# p128.net
KiCad netlist of a schematic drawn in EAGLE
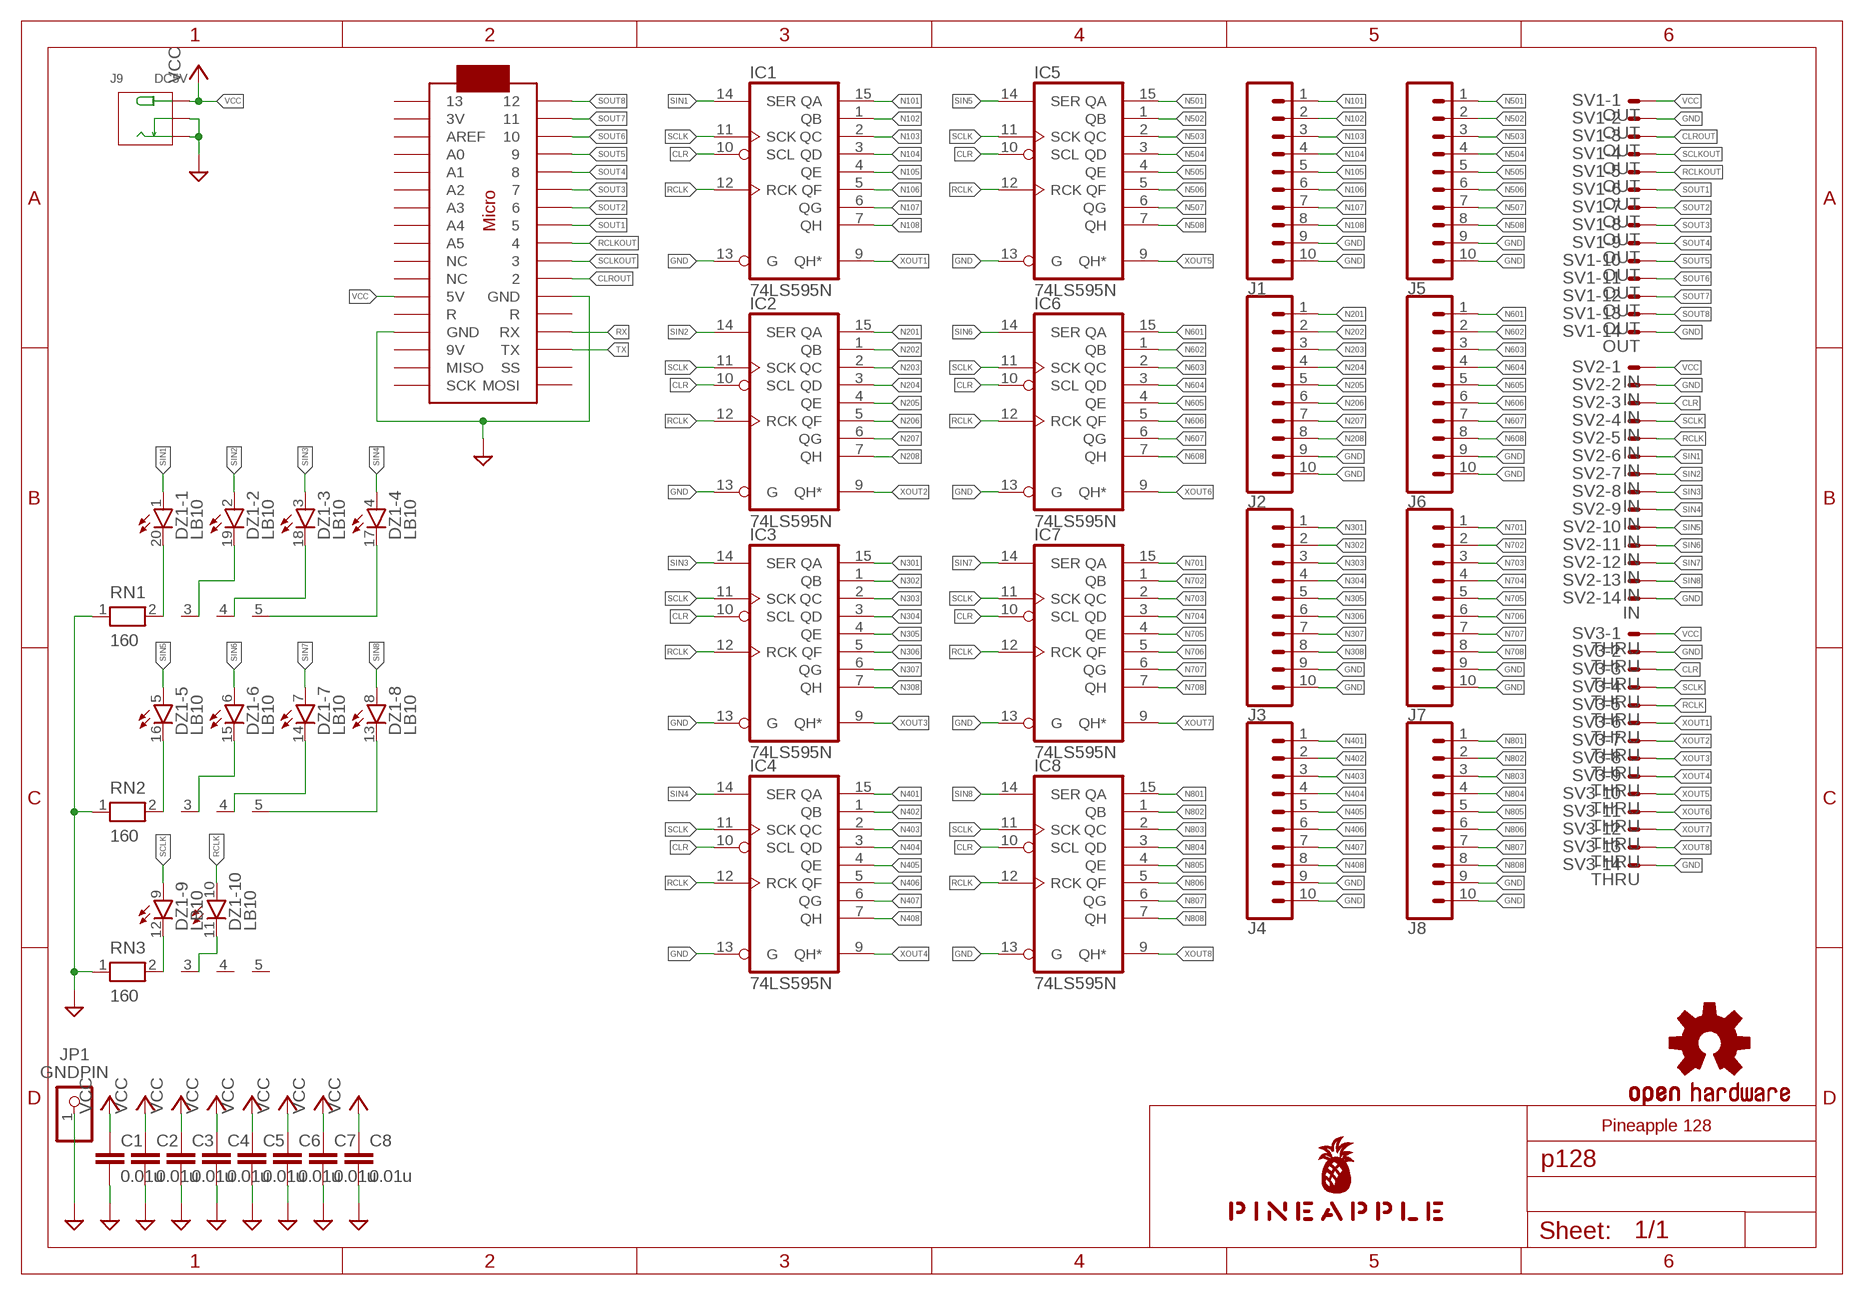
[diagram p0: schematic, sheet 1]

(export (version "E")
  (design (tool "Eeschema 10.0.6"))
  (components
    (comp (ref "C1")
      (value "0.01u")
      (footprint "eagle-import:C025-024X044")
      (libsource (lib "eagle-import") (part "C-EU025-024X044"))
    )
    (comp (ref "C2")
      (value "0.01u")
      (footprint "eagle-import:C025-024X044")
      (libsource (lib "eagle-import") (part "C-EU025-024X044"))
    )
    (comp (ref "C3")
      (value "0.01u")
      (footprint "eagle-import:C025-024X044")
      (libsource (lib "eagle-import") (part "C-EU025-024X044"))
    )
    (comp (ref "C4")
      (value "0.01u")
      (footprint "eagle-import:C025-024X044")
      (libsource (lib "eagle-import") (part "C-EU025-024X044"))
    )
    (comp (ref "C5")
      (value "0.01u")
      (footprint "eagle-import:C025-024X044")
      (libsource (lib "eagle-import") (part "C-EU025-024X044"))
    )
    (comp (ref "C6")
      (value "0.01u")
      (footprint "eagle-import:C025-024X044")
      (libsource (lib "eagle-import") (part "C-EU025-024X044"))
    )
    (comp (ref "C7")
      (value "0.01u")
      (footprint "eagle-import:C025-024X044")
      (libsource (lib "eagle-import") (part "C-EU025-024X044"))
    )
    (comp (ref "C8")
      (value "0.01u")
      (footprint "eagle-import:C025-024X044")
      (libsource (lib "eagle-import") (part "C-EU025-024X044"))
    )
    (comp (ref "DZ1")
      (value "LB10")
      (footprint "eagle-import:LB10")
      (libsource (lib "eagle-import") (part "LB10"))
    )
    (comp (ref "IC1")
      (value "74LS595N")
      (footprint "eagle-import:DIL16")
      (libsource (lib "eagle-import") (part "74595NLS"))
    )
    (comp (ref "IC2")
      (value "74LS595N")
      (footprint "eagle-import:DIL16")
      (libsource (lib "eagle-import") (part "74595NLS"))
    )
    (comp (ref "IC3")
      (value "74LS595N")
      (footprint "eagle-import:DIL16")
      (libsource (lib "eagle-import") (part "74595NLS"))
    )
    (comp (ref "IC4")
      (value "74LS595N")
      (footprint "eagle-import:DIL16")
      (libsource (lib "eagle-import") (part "74595NLS"))
    )
    (comp (ref "IC5")
      (value "74LS595N")
      (footprint "eagle-import:DIL16")
      (libsource (lib "eagle-import") (part "74595NLS"))
    )
    (comp (ref "IC6")
      (value "74LS595N")
      (footprint "eagle-import:DIL16")
      (libsource (lib "eagle-import") (part "74595NLS"))
    )
    (comp (ref "IC7")
      (value "74LS595N")
      (footprint "eagle-import:DIL16")
      (libsource (lib "eagle-import") (part "74595NLS"))
    )
    (comp (ref "IC8")
      (value "74LS595N")
      (footprint "eagle-import:DIL16")
      (libsource (lib "eagle-import") (part "74595NLS"))
    )
    (comp (ref "J1")
      (value "CONN_10\"")
      (footprint "eagle-import:1X10")
      (libsource (lib "eagle-import") (part "CONN_10{dblquote}"))
    )
    (comp (ref "J2")
      (value "CONN_10\"")
      (footprint "eagle-import:1X10")
      (libsource (lib "eagle-import") (part "CONN_10{dblquote}"))
    )
    (comp (ref "J3")
      (value "CONN_10\"")
      (footprint "eagle-import:1X10")
      (libsource (lib "eagle-import") (part "CONN_10{dblquote}"))
    )
    (comp (ref "J4")
      (value "CONN_10\"")
      (footprint "eagle-import:1X10")
      (libsource (lib "eagle-import") (part "CONN_10{dblquote}"))
    )
    (comp (ref "J5")
      (value "CONN_10\"")
      (footprint "eagle-import:1X10")
      (libsource (lib "eagle-import") (part "CONN_10{dblquote}"))
    )
    (comp (ref "J6")
      (value "CONN_10\"")
      (footprint "eagle-import:1X10")
      (libsource (lib "eagle-import") (part "CONN_10{dblquote}"))
    )
    (comp (ref "J7")
      (value "CONN_10\"")
      (footprint "eagle-import:1X10")
      (libsource (lib "eagle-import") (part "CONN_10{dblquote}"))
    )
    (comp (ref "J8")
      (value "CONN_10\"")
      (footprint "eagle-import:1X10")
      (libsource (lib "eagle-import") (part "CONN_10{dblquote}"))
    )
    (comp (ref "J9")
      (value "DC5V")
      (footprint "eagle-import:3P-L14.2_W11.0_H9.0MM")
      (libsource (lib "eagle-import") (part "JACK-DC-005'DC-005'"))
    )
    (comp (ref "JP1")
      (value "GNDPIN")
      (footprint "eagle-import:1X01")
      (libsource (lib "eagle-import") (part "PINHD-1X1"))
    )
    (comp (ref "LOGO1")
      (value "OSHW-LOGOS-COPPER")
      (footprint "eagle-import:OSHW-LOGO-S_COPPER")
      (libsource (lib "eagle-import") (part "OSHW-LOGOS-COPPER"))
    )
    (comp (ref "RN1")
      (value "160")
      (footprint "eagle-import:RN-5")
      (libsource (lib "eagle-import") (part "RN04"))
    )
    (comp (ref "RN2")
      (value "160")
      (footprint "eagle-import:RN-5")
      (libsource (lib "eagle-import") (part "RN04"))
    )
    (comp (ref "RN3")
      (value "160")
      (footprint "eagle-import:RN-5")
      (libsource (lib "eagle-import") (part "RN04"))
    )
    (comp (ref "SV1")
      (value "OUT")
      (footprint "eagle-import:ML14")
      (libsource (lib "eagle-import") (part "ML14E"))
    )
    (comp (ref "SV2")
      (value "IN")
      (footprint "eagle-import:ML14")
      (libsource (lib "eagle-import") (part "ML14E"))
    )
    (comp (ref "SV3")
      (value "THRU")
      (footprint "eagle-import:ML14")
      (libsource (lib "eagle-import") (part "ML14E"))
    )
    (comp (ref "U$1")
      (value "PINEAPPLE450_SILK")
      (footprint "eagle-import:PINEAPPLE450_SILK")
      (libsource (lib "eagle-import") (part "PINEAPPLE450_SILK"))
    )
    (comp (ref "U$2")
      (value "ARDUINOMICRO")
      (footprint "eagle-import:ARDUINOMICRO")
      (libsource (lib "eagle-import") (part "ARDUINOMICRO"))
    )
  )
  (nets
    (net (code "1") (name "CLR") (class "Default")
      (node (ref "IC1") (pin "10") (pinfunction "SCL_10") (pintype "input"))
      (node (ref "IC2") (pin "10") (pinfunction "SCL_10") (pintype "input"))
      (node (ref "IC3") (pin "10") (pinfunction "SCL_10") (pintype "input"))
      (node (ref "IC4") (pin "10") (pinfunction "SCL_10") (pintype "input"))
      (node (ref "IC5") (pin "10") (pinfunction "SCL_10") (pintype "input"))
      (node (ref "IC6") (pin "10") (pinfunction "SCL_10") (pintype "input"))
      (node (ref "IC7") (pin "10") (pinfunction "SCL_10") (pintype "input"))
      (node (ref "IC8") (pin "10") (pinfunction "SCL_10") (pintype "input"))
      (node (ref "SV2") (pin "3") (pinfunction "S_3") (pintype "passive"))
      (node (ref "SV3") (pin "3") (pinfunction "S_3") (pintype "passive"))
    )
    (net (code "2") (name "CLROUT") (class "Default")
      (node (ref "SV1") (pin "3") (pinfunction "S_3") (pintype "passive"))
      (node (ref "U$2") (pin "P$11") (pinfunction "2_P$11") (pintype "bidirectional"))
    )
    (net (code "3") (name "GND") (class "Default")
      (node (ref "C1") (pin "2") (pinfunction "2_2") (pintype "passive"))
      (node (ref "C2") (pin "2") (pinfunction "2_2") (pintype "passive"))
      (node (ref "C3") (pin "2") (pinfunction "2_2") (pintype "passive"))
      (node (ref "C4") (pin "2") (pinfunction "2_2") (pintype "passive"))
      (node (ref "C5") (pin "2") (pinfunction "2_2") (pintype "passive"))
      (node (ref "C6") (pin "2") (pinfunction "2_2") (pintype "passive"))
      (node (ref "C7") (pin "2") (pinfunction "2_2") (pintype "passive"))
      (node (ref "C8") (pin "2") (pinfunction "2_2") (pintype "passive"))
      (node (ref "IC1") (pin "13") (pinfunction "G_13") (pintype "input"))
      (node (ref "IC2") (pin "13") (pinfunction "G_13") (pintype "input"))
      (node (ref "IC3") (pin "13") (pinfunction "G_13") (pintype "input"))
      (node (ref "IC4") (pin "13") (pinfunction "G_13") (pintype "input"))
      (node (ref "IC5") (pin "13") (pinfunction "G_13") (pintype "input"))
      (node (ref "IC6") (pin "13") (pinfunction "G_13") (pintype "input"))
      (node (ref "IC7") (pin "13") (pinfunction "G_13") (pintype "input"))
      (node (ref "IC8") (pin "13") (pinfunction "G_13") (pintype "input"))
      (node (ref "J1") (pin "10") (pinfunction "10_10") (pintype "passive"))
      (node (ref "J1") (pin "9") (pinfunction "9_9") (pintype "passive"))
      (node (ref "J2") (pin "10") (pinfunction "10_10") (pintype "passive"))
      (node (ref "J2") (pin "9") (pinfunction "9_9") (pintype "passive"))
      (node (ref "J3") (pin "10") (pinfunction "10_10") (pintype "passive"))
      (node (ref "J3") (pin "9") (pinfunction "9_9") (pintype "passive"))
      (node (ref "J4") (pin "10") (pinfunction "10_10") (pintype "passive"))
      (node (ref "J4") (pin "9") (pinfunction "9_9") (pintype "passive"))
      (node (ref "J5") (pin "10") (pinfunction "10_10") (pintype "passive"))
      (node (ref "J5") (pin "9") (pinfunction "9_9") (pintype "passive"))
      (node (ref "J6") (pin "10") (pinfunction "10_10") (pintype "passive"))
      (node (ref "J6") (pin "9") (pinfunction "9_9") (pintype "passive"))
      (node (ref "J7") (pin "10") (pinfunction "10_10") (pintype "passive"))
      (node (ref "J7") (pin "9") (pinfunction "9_9") (pintype "passive"))
      (node (ref "J8") (pin "10") (pinfunction "10_10") (pintype "passive"))
      (node (ref "J8") (pin "9") (pinfunction "9_9") (pintype "passive"))
      (node (ref "J9") (pin "-1") (pinfunction "-_-1") (pintype "bidirectional"))
      (node (ref "J9") (pin "-2") (pinfunction "CDN_-2") (pintype "bidirectional"))
      (node (ref "JP1") (pin "1") (pinfunction "1_1") (pintype "passive"))
      (node (ref "RN1") (pin "1") (pinfunction "1_1") (pintype "passive"))
      (node (ref "RN2") (pin "1") (pinfunction "1_1") (pintype "passive"))
      (node (ref "RN3") (pin "1") (pinfunction "1_1") (pintype "passive"))
      (node (ref "SV1") (pin "14") (pinfunction "S_14") (pintype "passive"))
      (node (ref "SV1") (pin "2") (pinfunction "S_2") (pintype "passive"))
      (node (ref "SV2") (pin "14") (pinfunction "S_14") (pintype "passive"))
      (node (ref "SV2") (pin "2") (pinfunction "S_2") (pintype "passive"))
      (node (ref "SV3") (pin "14") (pinfunction "S_14") (pintype "passive"))
      (node (ref "SV3") (pin "2") (pinfunction "S_2") (pintype "passive"))
      (node (ref "U$2") (pin "P$12") (pinfunction "GND_P$12") (pintype "bidirectional"))
      (node (ref "U$2") (pin "P$21") (pinfunction "GND_P$21") (pintype "bidirectional"))
    )
    (net (code "4") (name "N101") (class "Default")
      (node (ref "IC1") (pin "15") (pinfunction "QA_15") (pintype "tri_state"))
      (node (ref "J1") (pin "1") (pinfunction "1_1") (pintype "passive"))
    )
    (net (code "5") (name "N102") (class "Default")
      (node (ref "IC1") (pin "1") (pinfunction "QB_1") (pintype "tri_state"))
      (node (ref "J1") (pin "2") (pinfunction "2_2") (pintype "passive"))
    )
    (net (code "6") (name "N103") (class "Default")
      (node (ref "IC1") (pin "2") (pinfunction "QC_2") (pintype "tri_state"))
      (node (ref "J1") (pin "3") (pinfunction "3_3") (pintype "passive"))
    )
    (net (code "7") (name "N104") (class "Default")
      (node (ref "IC1") (pin "3") (pinfunction "QD_3") (pintype "tri_state"))
      (node (ref "J1") (pin "4") (pinfunction "4_4") (pintype "passive"))
    )
    (net (code "8") (name "N105") (class "Default")
      (node (ref "IC1") (pin "4") (pinfunction "QE_4") (pintype "tri_state"))
      (node (ref "J1") (pin "5") (pinfunction "5_5") (pintype "passive"))
    )
    (net (code "9") (name "N106") (class "Default")
      (node (ref "IC1") (pin "5") (pinfunction "QF_5") (pintype "tri_state"))
      (node (ref "J1") (pin "6") (pinfunction "6_6") (pintype "passive"))
    )
    (net (code "10") (name "N107") (class "Default")
      (node (ref "IC1") (pin "6") (pinfunction "QG_6") (pintype "tri_state"))
      (node (ref "J1") (pin "7") (pinfunction "7_7") (pintype "passive"))
    )
    (net (code "11") (name "N108") (class "Default")
      (node (ref "IC1") (pin "7") (pinfunction "QH_7") (pintype "tri_state"))
      (node (ref "J1") (pin "8") (pinfunction "8_8") (pintype "passive"))
    )
    (net (code "12") (name "N201") (class "Default")
      (node (ref "IC2") (pin "15") (pinfunction "QA_15") (pintype "tri_state"))
      (node (ref "J2") (pin "1") (pinfunction "1_1") (pintype "passive"))
    )
    (net (code "13") (name "N202") (class "Default")
      (node (ref "IC2") (pin "1") (pinfunction "QB_1") (pintype "tri_state"))
      (node (ref "J2") (pin "2") (pinfunction "2_2") (pintype "passive"))
    )
    (net (code "14") (name "N203") (class "Default")
      (node (ref "IC2") (pin "2") (pinfunction "QC_2") (pintype "tri_state"))
      (node (ref "J2") (pin "3") (pinfunction "3_3") (pintype "passive"))
    )
    (net (code "15") (name "N204") (class "Default")
      (node (ref "IC2") (pin "3") (pinfunction "QD_3") (pintype "tri_state"))
      (node (ref "J2") (pin "4") (pinfunction "4_4") (pintype "passive"))
    )
    (net (code "16") (name "N205") (class "Default")
      (node (ref "IC2") (pin "4") (pinfunction "QE_4") (pintype "tri_state"))
      (node (ref "J2") (pin "5") (pinfunction "5_5") (pintype "passive"))
    )
    (net (code "17") (name "N206") (class "Default")
      (node (ref "IC2") (pin "5") (pinfunction "QF_5") (pintype "tri_state"))
      (node (ref "J2") (pin "6") (pinfunction "6_6") (pintype "passive"))
    )
    (net (code "18") (name "N207") (class "Default")
      (node (ref "IC2") (pin "6") (pinfunction "QG_6") (pintype "tri_state"))
      (node (ref "J2") (pin "7") (pinfunction "7_7") (pintype "passive"))
    )
    (net (code "19") (name "N208") (class "Default")
      (node (ref "IC2") (pin "7") (pinfunction "QH_7") (pintype "tri_state"))
      (node (ref "J2") (pin "8") (pinfunction "8_8") (pintype "passive"))
    )
    (net (code "20") (name "N301") (class "Default")
      (node (ref "IC3") (pin "15") (pinfunction "QA_15") (pintype "tri_state"))
      (node (ref "J3") (pin "1") (pinfunction "1_1") (pintype "passive"))
    )
    (net (code "21") (name "N302") (class "Default")
      (node (ref "IC3") (pin "1") (pinfunction "QB_1") (pintype "tri_state"))
      (node (ref "J3") (pin "2") (pinfunction "2_2") (pintype "passive"))
    )
    (net (code "22") (name "N303") (class "Default")
      (node (ref "IC3") (pin "2") (pinfunction "QC_2") (pintype "tri_state"))
      (node (ref "J3") (pin "3") (pinfunction "3_3") (pintype "passive"))
    )
    (net (code "23") (name "N304") (class "Default")
      (node (ref "IC3") (pin "3") (pinfunction "QD_3") (pintype "tri_state"))
      (node (ref "J3") (pin "4") (pinfunction "4_4") (pintype "passive"))
    )
    (net (code "24") (name "N305") (class "Default")
      (node (ref "IC3") (pin "4") (pinfunction "QE_4") (pintype "tri_state"))
      (node (ref "J3") (pin "5") (pinfunction "5_5") (pintype "passive"))
    )
    (net (code "25") (name "N306") (class "Default")
      (node (ref "IC3") (pin "5") (pinfunction "QF_5") (pintype "tri_state"))
      (node (ref "J3") (pin "6") (pinfunction "6_6") (pintype "passive"))
    )
    (net (code "26") (name "N307") (class "Default")
      (node (ref "IC3") (pin "6") (pinfunction "QG_6") (pintype "tri_state"))
      (node (ref "J3") (pin "7") (pinfunction "7_7") (pintype "passive"))
    )
    (net (code "27") (name "N308") (class "Default")
      (node (ref "IC3") (pin "7") (pinfunction "QH_7") (pintype "tri_state"))
      (node (ref "J3") (pin "8") (pinfunction "8_8") (pintype "passive"))
    )
    (net (code "28") (name "N401") (class "Default")
      (node (ref "IC4") (pin "15") (pinfunction "QA_15") (pintype "tri_state"))
      (node (ref "J4") (pin "1") (pinfunction "1_1") (pintype "passive"))
    )
    (net (code "29") (name "N402") (class "Default")
      (node (ref "IC4") (pin "1") (pinfunction "QB_1") (pintype "tri_state"))
      (node (ref "J4") (pin "2") (pinfunction "2_2") (pintype "passive"))
    )
    (net (code "30") (name "N403") (class "Default")
      (node (ref "IC4") (pin "2") (pinfunction "QC_2") (pintype "tri_state"))
      (node (ref "J4") (pin "3") (pinfunction "3_3") (pintype "passive"))
    )
    (net (code "31") (name "N404") (class "Default")
      (node (ref "IC4") (pin "3") (pinfunction "QD_3") (pintype "tri_state"))
      (node (ref "J4") (pin "4") (pinfunction "4_4") (pintype "passive"))
    )
    (net (code "32") (name "N405") (class "Default")
      (node (ref "IC4") (pin "4") (pinfunction "QE_4") (pintype "tri_state"))
      (node (ref "J4") (pin "5") (pinfunction "5_5") (pintype "passive"))
    )
    (net (code "33") (name "N406") (class "Default")
      (node (ref "IC4") (pin "5") (pinfunction "QF_5") (pintype "tri_state"))
      (node (ref "J4") (pin "6") (pinfunction "6_6") (pintype "passive"))
    )
    (net (code "34") (name "N407") (class "Default")
      (node (ref "IC4") (pin "6") (pinfunction "QG_6") (pintype "tri_state"))
      (node (ref "J4") (pin "7") (pinfunction "7_7") (pintype "passive"))
    )
    (net (code "35") (name "N408") (class "Default")
      (node (ref "IC4") (pin "7") (pinfunction "QH_7") (pintype "tri_state"))
      (node (ref "J4") (pin "8") (pinfunction "8_8") (pintype "passive"))
    )
    (net (code "36") (name "N501") (class "Default")
      (node (ref "IC5") (pin "15") (pinfunction "QA_15") (pintype "tri_state"))
      (node (ref "J5") (pin "1") (pinfunction "1_1") (pintype "passive"))
    )
    (net (code "37") (name "N502") (class "Default")
      (node (ref "IC5") (pin "1") (pinfunction "QB_1") (pintype "tri_state"))
      (node (ref "J5") (pin "2") (pinfunction "2_2") (pintype "passive"))
    )
    (net (code "38") (name "N503") (class "Default")
      (node (ref "IC5") (pin "2") (pinfunction "QC_2") (pintype "tri_state"))
      (node (ref "J5") (pin "3") (pinfunction "3_3") (pintype "passive"))
    )
    (net (code "39") (name "N504") (class "Default")
      (node (ref "IC5") (pin "3") (pinfunction "QD_3") (pintype "tri_state"))
      (node (ref "J5") (pin "4") (pinfunction "4_4") (pintype "passive"))
    )
    (net (code "40") (name "N505") (class "Default")
      (node (ref "IC5") (pin "4") (pinfunction "QE_4") (pintype "tri_state"))
      (node (ref "J5") (pin "5") (pinfunction "5_5") (pintype "passive"))
    )
    (net (code "41") (name "N506") (class "Default")
      (node (ref "IC5") (pin "5") (pinfunction "QF_5") (pintype "tri_state"))
      (node (ref "J5") (pin "6") (pinfunction "6_6") (pintype "passive"))
    )
    (net (code "42") (name "N507") (class "Default")
      (node (ref "IC5") (pin "6") (pinfunction "QG_6") (pintype "tri_state"))
      (node (ref "J5") (pin "7") (pinfunction "7_7") (pintype "passive"))
    )
    (net (code "43") (name "N508") (class "Default")
      (node (ref "IC5") (pin "7") (pinfunction "QH_7") (pintype "tri_state"))
      (node (ref "J5") (pin "8") (pinfunction "8_8") (pintype "passive"))
    )
    (net (code "44") (name "N601") (class "Default")
      (node (ref "IC6") (pin "15") (pinfunction "QA_15") (pintype "tri_state"))
      (node (ref "J6") (pin "1") (pinfunction "1_1") (pintype "passive"))
    )
    (net (code "45") (name "N602") (class "Default")
      (node (ref "IC6") (pin "1") (pinfunction "QB_1") (pintype "tri_state"))
      (node (ref "J6") (pin "2") (pinfunction "2_2") (pintype "passive"))
    )
    (net (code "46") (name "N603") (class "Default")
      (node (ref "IC6") (pin "2") (pinfunction "QC_2") (pintype "tri_state"))
      (node (ref "J6") (pin "3") (pinfunction "3_3") (pintype "passive"))
    )
    (net (code "47") (name "N604") (class "Default")
      (node (ref "IC6") (pin "3") (pinfunction "QD_3") (pintype "tri_state"))
      (node (ref "J6") (pin "4") (pinfunction "4_4") (pintype "passive"))
    )
    (net (code "48") (name "N605") (class "Default")
      (node (ref "IC6") (pin "4") (pinfunction "QE_4") (pintype "tri_state"))
      (node (ref "J6") (pin "5") (pinfunction "5_5") (pintype "passive"))
    )
    (net (code "49") (name "N606") (class "Default")
      (node (ref "IC6") (pin "5") (pinfunction "QF_5") (pintype "tri_state"))
      (node (ref "J6") (pin "6") (pinfunction "6_6") (pintype "passive"))
    )
    (net (code "50") (name "N607") (class "Default")
      (node (ref "IC6") (pin "6") (pinfunction "QG_6") (pintype "tri_state"))
      (node (ref "J6") (pin "7") (pinfunction "7_7") (pintype "passive"))
    )
    (net (code "51") (name "N608") (class "Default")
      (node (ref "IC6") (pin "7") (pinfunction "QH_7") (pintype "tri_state"))
      (node (ref "J6") (pin "8") (pinfunction "8_8") (pintype "passive"))
    )
    (net (code "52") (name "N701") (class "Default")
      (node (ref "IC7") (pin "15") (pinfunction "QA_15") (pintype "tri_state"))
      (node (ref "J7") (pin "1") (pinfunction "1_1") (pintype "passive"))
    )
    (net (code "53") (name "N702") (class "Default")
      (node (ref "IC7") (pin "1") (pinfunction "QB_1") (pintype "tri_state"))
      (node (ref "J7") (pin "2") (pinfunction "2_2") (pintype "passive"))
    )
    (net (code "54") (name "N703") (class "Default")
      (node (ref "IC7") (pin "2") (pinfunction "QC_2") (pintype "tri_state"))
      (node (ref "J7") (pin "3") (pinfunction "3_3") (pintype "passive"))
    )
    (net (code "55") (name "N704") (class "Default")
      (node (ref "IC7") (pin "3") (pinfunction "QD_3") (pintype "tri_state"))
      (node (ref "J7") (pin "4") (pinfunction "4_4") (pintype "passive"))
    )
    (net (code "56") (name "N705") (class "Default")
      (node (ref "IC7") (pin "4") (pinfunction "QE_4") (pintype "tri_state"))
      (node (ref "J7") (pin "5") (pinfunction "5_5") (pintype "passive"))
    )
    (net (code "57") (name "N706") (class "Default")
      (node (ref "IC7") (pin "5") (pinfunction "QF_5") (pintype "tri_state"))
      (node (ref "J7") (pin "6") (pinfunction "6_6") (pintype "passive"))
    )
    (net (code "58") (name "N707") (class "Default")
      (node (ref "IC7") (pin "6") (pinfunction "QG_6") (pintype "tri_state"))
      (node (ref "J7") (pin "7") (pinfunction "7_7") (pintype "passive"))
    )
    (net (code "59") (name "N708") (class "Default")
      (node (ref "IC7") (pin "7") (pinfunction "QH_7") (pintype "tri_state"))
      (node (ref "J7") (pin "8") (pinfunction "8_8") (pintype "passive"))
    )
    (net (code "60") (name "N801") (class "Default")
      (node (ref "IC8") (pin "15") (pinfunction "QA_15") (pintype "tri_state"))
      (node (ref "J8") (pin "1") (pinfunction "1_1") (pintype "passive"))
    )
    (net (code "61") (name "N802") (class "Default")
      (node (ref "IC8") (pin "1") (pinfunction "QB_1") (pintype "tri_state"))
      (node (ref "J8") (pin "2") (pinfunction "2_2") (pintype "passive"))
    )
    (net (code "62") (name "N803") (class "Default")
      (node (ref "IC8") (pin "2") (pinfunction "QC_2") (pintype "tri_state"))
      (node (ref "J8") (pin "3") (pinfunction "3_3") (pintype "passive"))
    )
    (net (code "63") (name "N804") (class "Default")
      (node (ref "IC8") (pin "3") (pinfunction "QD_3") (pintype "tri_state"))
      (node (ref "J8") (pin "4") (pinfunction "4_4") (pintype "passive"))
    )
    (net (code "64") (name "N805") (class "Default")
      (node (ref "IC8") (pin "4") (pinfunction "QE_4") (pintype "tri_state"))
      (node (ref "J8") (pin "5") (pinfunction "5_5") (pintype "passive"))
    )
    (net (code "65") (name "N806") (class "Default")
      (node (ref "IC8") (pin "5") (pinfunction "QF_5") (pintype "tri_state"))
      (node (ref "J8") (pin "6") (pinfunction "6_6") (pintype "passive"))
    )
    (net (code "66") (name "N807") (class "Default")
      (node (ref "IC8") (pin "6") (pinfunction "QG_6") (pintype "tri_state"))
      (node (ref "J8") (pin "7") (pinfunction "7_7") (pintype "passive"))
    )
    (net (code "67") (name "N808") (class "Default")
      (node (ref "IC8") (pin "7") (pinfunction "QH_7") (pintype "tri_state"))
      (node (ref "J8") (pin "8") (pinfunction "8_8") (pintype "passive"))
    )
    (net (code "68") (name "Net-(DZ1A-C)") (class "Default")
      (node (ref "DZ1") (pin "20") (pinfunction "C_20") (pintype "passive"))
      (node (ref "RN1") (pin "2") (pinfunction "2_2") (pintype "passive"))
    )
    (net (code "69") (name "Net-(DZ1B-C)") (class "Default")
      (node (ref "DZ1") (pin "11") (pinfunction "C_11") (pintype "passive"))
      (node (ref "RN3") (pin "3") (pinfunction "3_3") (pintype "passive"))
    )
    (net (code "70") (name "Net-(DZ1C-C)") (class "Default")
      (node (ref "DZ1") (pin "19") (pinfunction "C_19") (pintype "passive"))
      (node (ref "RN1") (pin "3") (pinfunction "3_3") (pintype "passive"))
    )
    (net (code "71") (name "Net-(DZ1D-C)") (class "Default")
      (node (ref "DZ1") (pin "18") (pinfunction "C_18") (pintype "passive"))
      (node (ref "RN1") (pin "4") (pinfunction "4_4") (pintype "passive"))
    )
    (net (code "72") (name "Net-(DZ1E-C)") (class "Default")
      (node (ref "DZ1") (pin "17") (pinfunction "C_17") (pintype "passive"))
      (node (ref "RN1") (pin "5") (pinfunction "5_5") (pintype "passive"))
    )
    (net (code "73") (name "Net-(DZ1F-C)") (class "Default")
      (node (ref "DZ1") (pin "16") (pinfunction "C_16") (pintype "passive"))
      (node (ref "RN2") (pin "2") (pinfunction "2_2") (pintype "passive"))
    )
    (net (code "74") (name "Net-(DZ1G-C)") (class "Default")
      (node (ref "DZ1") (pin "15") (pinfunction "C_15") (pintype "passive"))
      (node (ref "RN2") (pin "3") (pinfunction "3_3") (pintype "passive"))
    )
    (net (code "75") (name "Net-(DZ1H-C)") (class "Default")
      (node (ref "DZ1") (pin "14") (pinfunction "C_14") (pintype "passive"))
      (node (ref "RN2") (pin "4") (pinfunction "4_4") (pintype "passive"))
    )
    (net (code "76") (name "Net-(DZ1I-C)") (class "Default")
      (node (ref "DZ1") (pin "13") (pinfunction "C_13") (pintype "passive"))
      (node (ref "RN2") (pin "5") (pinfunction "5_5") (pintype "passive"))
    )
    (net (code "77") (name "Net-(DZ1J-C)") (class "Default")
      (node (ref "DZ1") (pin "12") (pinfunction "C_12") (pintype "passive"))
      (node (ref "RN3") (pin "2") (pinfunction "2_2") (pintype "passive"))
    )
    (net (code "78") (name "RCLK") (class "Default")
      (node (ref "DZ1") (pin "10") (pinfunction "A_10") (pintype "passive"))
      (node (ref "IC1") (pin "12") (pinfunction "RCK_12") (pintype "input"))
      (node (ref "IC2") (pin "12") (pinfunction "RCK_12") (pintype "input"))
      (node (ref "IC3") (pin "12") (pinfunction "RCK_12") (pintype "input"))
      (node (ref "IC4") (pin "12") (pinfunction "RCK_12") (pintype "input"))
      (node (ref "IC5") (pin "12") (pinfunction "RCK_12") (pintype "input"))
      (node (ref "IC6") (pin "12") (pinfunction "RCK_12") (pintype "input"))
      (node (ref "IC7") (pin "12") (pinfunction "RCK_12") (pintype "input"))
      (node (ref "IC8") (pin "12") (pinfunction "RCK_12") (pintype "input"))
      (node (ref "SV2") (pin "5") (pinfunction "S_5") (pintype "passive"))
      (node (ref "SV3") (pin "5") (pinfunction "S_5") (pintype "passive"))
    )
    (net (code "79") (name "RCLKOUT") (class "Default")
      (node (ref "SV1") (pin "5") (pinfunction "S_5") (pintype "passive"))
      (node (ref "U$2") (pin "P$9") (pinfunction "4_P$9") (pintype "bidirectional"))
    )
    (net (code "80") (name "RX") (class "Default")
      (node (ref "U$2") (pin "P$14") (pinfunction "RX_P$14") (pintype "bidirectional"))
    )
    (net (code "81") (name "SCLK") (class "Default")
      (node (ref "DZ1") (pin "9") (pinfunction "A_9") (pintype "passive"))
      (node (ref "IC1") (pin "11") (pinfunction "SCK_11") (pintype "input"))
      (node (ref "IC2") (pin "11") (pinfunction "SCK_11") (pintype "input"))
      (node (ref "IC3") (pin "11") (pinfunction "SCK_11") (pintype "input"))
      (node (ref "IC4") (pin "11") (pinfunction "SCK_11") (pintype "input"))
      (node (ref "IC5") (pin "11") (pinfunction "SCK_11") (pintype "input"))
      (node (ref "IC6") (pin "11") (pinfunction "SCK_11") (pintype "input"))
      (node (ref "IC7") (pin "11") (pinfunction "SCK_11") (pintype "input"))
      (node (ref "IC8") (pin "11") (pinfunction "SCK_11") (pintype "input"))
      (node (ref "SV2") (pin "4") (pinfunction "S_4") (pintype "passive"))
      (node (ref "SV3") (pin "4") (pinfunction "S_4") (pintype "passive"))
    )
    (net (code "82") (name "SCLKOUT") (class "Default")
      (node (ref "SV1") (pin "4") (pinfunction "S_4") (pintype "passive"))
      (node (ref "U$2") (pin "P$10") (pinfunction "3_P$10") (pintype "bidirectional"))
    )
    (net (code "83") (name "SIN1") (class "Default")
      (node (ref "DZ1") (pin "1") (pinfunction "A_1") (pintype "passive"))
      (node (ref "IC1") (pin "14") (pinfunction "SER_14") (pintype "input"))
      (node (ref "SV2") (pin "6") (pinfunction "S_6") (pintype "passive"))
    )
    (net (code "84") (name "SIN2") (class "Default")
      (node (ref "DZ1") (pin "2") (pinfunction "A_2") (pintype "passive"))
      (node (ref "IC2") (pin "14") (pinfunction "SER_14") (pintype "input"))
      (node (ref "SV2") (pin "7") (pinfunction "S_7") (pintype "passive"))
    )
    (net (code "85") (name "SIN3") (class "Default")
      (node (ref "DZ1") (pin "3") (pinfunction "A_3") (pintype "passive"))
      (node (ref "IC3") (pin "14") (pinfunction "SER_14") (pintype "input"))
      (node (ref "SV2") (pin "8") (pinfunction "S_8") (pintype "passive"))
    )
    (net (code "86") (name "SIN4") (class "Default")
      (node (ref "DZ1") (pin "4") (pinfunction "A_4") (pintype "passive"))
      (node (ref "IC4") (pin "14") (pinfunction "SER_14") (pintype "input"))
      (node (ref "SV2") (pin "9") (pinfunction "S_9") (pintype "passive"))
    )
    (net (code "87") (name "SIN5") (class "Default")
      (node (ref "DZ1") (pin "5") (pinfunction "A_5") (pintype "passive"))
      (node (ref "IC5") (pin "14") (pinfunction "SER_14") (pintype "input"))
      (node (ref "SV2") (pin "10") (pinfunction "S_10") (pintype "passive"))
    )
    (net (code "88") (name "SIN6") (class "Default")
      (node (ref "DZ1") (pin "6") (pinfunction "A_6") (pintype "passive"))
      (node (ref "IC6") (pin "14") (pinfunction "SER_14") (pintype "input"))
      (node (ref "SV2") (pin "11") (pinfunction "S_11") (pintype "passive"))
    )
    (net (code "89") (name "SIN7") (class "Default")
      (node (ref "DZ1") (pin "7") (pinfunction "A_7") (pintype "passive"))
      (node (ref "IC7") (pin "14") (pinfunction "SER_14") (pintype "input"))
      (node (ref "SV2") (pin "12") (pinfunction "S_12") (pintype "passive"))
    )
    (net (code "90") (name "SIN8") (class "Default")
      (node (ref "DZ1") (pin "8") (pinfunction "A_8") (pintype "passive"))
      (node (ref "IC8") (pin "14") (pinfunction "SER_14") (pintype "input"))
      (node (ref "SV2") (pin "13") (pinfunction "S_13") (pintype "passive"))
    )
    (net (code "91") (name "SOUT1") (class "Default")
      (node (ref "SV1") (pin "6") (pinfunction "S_6") (pintype "passive"))
      (node (ref "U$2") (pin "P$8") (pinfunction "5_P$8") (pintype "bidirectional"))
    )
    (net (code "92") (name "SOUT2") (class "Default")
      (node (ref "SV1") (pin "7") (pinfunction "S_7") (pintype "passive"))
      (node (ref "U$2") (pin "P$7") (pinfunction "6_P$7") (pintype "bidirectional"))
    )
    (net (code "93") (name "SOUT3") (class "Default")
      (node (ref "SV1") (pin "8") (pinfunction "S_8") (pintype "passive"))
      (node (ref "U$2") (pin "P$6") (pinfunction "7_P$6") (pintype "bidirectional"))
    )
    (net (code "94") (name "SOUT4") (class "Default")
      (node (ref "SV1") (pin "9") (pinfunction "S_9") (pintype "passive"))
      (node (ref "U$2") (pin "P$5") (pinfunction "8_P$5") (pintype "bidirectional"))
    )
    (net (code "95") (name "SOUT5") (class "Default")
      (node (ref "SV1") (pin "10") (pinfunction "S_10") (pintype "passive"))
      (node (ref "U$2") (pin "P$4") (pinfunction "9_P$4") (pintype "bidirectional"))
    )
    (net (code "96") (name "SOUT6") (class "Default")
      (node (ref "SV1") (pin "11") (pinfunction "S_11") (pintype "passive"))
      (node (ref "U$2") (pin "P$3") (pinfunction "10_P$3") (pintype "bidirectional"))
    )
    (net (code "97") (name "SOUT7") (class "Default")
      (node (ref "SV1") (pin "12") (pinfunction "S_12") (pintype "passive"))
      (node (ref "U$2") (pin "P$2") (pinfunction "11_P$2") (pintype "bidirectional"))
    )
    (net (code "98") (name "SOUT8") (class "Default")
      (node (ref "SV1") (pin "13") (pinfunction "S_13") (pintype "passive"))
      (node (ref "U$2") (pin "P$1") (pinfunction "12_P$1") (pintype "bidirectional"))
    )
    (net (code "99") (name "TX") (class "Default")
      (node (ref "U$2") (pin "P$15") (pinfunction "TX_P$15") (pintype "bidirectional"))
    )
    (net (code "100") (name "VCC") (class "Default")
      (node (ref "C1") (pin "1") (pinfunction "1_1") (pintype "passive"))
      (node (ref "C2") (pin "1") (pinfunction "1_1") (pintype "passive"))
      (node (ref "C3") (pin "1") (pinfunction "1_1") (pintype "passive"))
      (node (ref "C4") (pin "1") (pinfunction "1_1") (pintype "passive"))
      (node (ref "C5") (pin "1") (pinfunction "1_1") (pintype "passive"))
      (node (ref "C6") (pin "1") (pinfunction "1_1") (pintype "passive"))
      (node (ref "C7") (pin "1") (pinfunction "1_1") (pintype "passive"))
      (node (ref "C8") (pin "1") (pinfunction "1_1") (pintype "passive"))
      (node (ref "J9") (pin "+") (pinfunction "+_+") (pintype "bidirectional"))
      (node (ref "SV1") (pin "1") (pinfunction "S_1") (pintype "passive"))
      (node (ref "SV2") (pin "1") (pinfunction "S_1") (pintype "passive"))
      (node (ref "SV3") (pin "1") (pinfunction "S_1") (pintype "passive"))
      (node (ref "U$2") (pin "P$23") (pinfunction "5V_P$23") (pintype "bidirectional"))
    )
    (net (code "101") (name "XOUT1") (class "Default")
      (node (ref "IC1") (pin "9") (pinfunction "QH*_9") (pintype "tri_state"))
      (node (ref "SV3") (pin "6") (pinfunction "S_6") (pintype "passive"))
    )
    (net (code "102") (name "XOUT2") (class "Default")
      (node (ref "IC2") (pin "9") (pinfunction "QH*_9") (pintype "tri_state"))
      (node (ref "SV3") (pin "7") (pinfunction "S_7") (pintype "passive"))
    )
    (net (code "103") (name "XOUT3") (class "Default")
      (node (ref "IC3") (pin "9") (pinfunction "QH*_9") (pintype "tri_state"))
      (node (ref "SV3") (pin "8") (pinfunction "S_8") (pintype "passive"))
    )
    (net (code "104") (name "XOUT4") (class "Default")
      (node (ref "IC4") (pin "9") (pinfunction "QH*_9") (pintype "tri_state"))
      (node (ref "SV3") (pin "9") (pinfunction "S_9") (pintype "passive"))
    )
    (net (code "105") (name "XOUT5") (class "Default")
      (node (ref "IC5") (pin "9") (pinfunction "QH*_9") (pintype "tri_state"))
      (node (ref "SV3") (pin "10") (pinfunction "S_10") (pintype "passive"))
    )
    (net (code "106") (name "XOUT6") (class "Default")
      (node (ref "IC6") (pin "9") (pinfunction "QH*_9") (pintype "tri_state"))
      (node (ref "SV3") (pin "11") (pinfunction "S_11") (pintype "passive"))
    )
    (net (code "107") (name "XOUT7") (class "Default")
      (node (ref "IC7") (pin "9") (pinfunction "QH*_9") (pintype "tri_state"))
      (node (ref "SV3") (pin "12") (pinfunction "S_12") (pintype "passive"))
    )
    (net (code "108") (name "XOUT8") (class "Default")
      (node (ref "IC8") (pin "9") (pinfunction "QH*_9") (pintype "tri_state"))
      (node (ref "SV3") (pin "13") (pinfunction "S_13") (pintype "passive"))
    )
    (net (code "109") (name "unconnected-(RN3-Pad4)") (class "Default")
      (node (ref "RN3") (pin "4") (pinfunction "4_4") (pintype "passive"))
    )
    (net (code "110") (name "unconnected-(RN3-Pad5)") (class "Default")
      (node (ref "RN3") (pin "5") (pinfunction "5_5") (pintype "passive"))
    )
    (net (code "111") (name "unconnected-(U$2-3V-PadP$33)") (class "Default")
      (node (ref "U$2") (pin "P$33") (pinfunction "3V_P$33") (pintype "bidirectional"))
    )
    (net (code "112") (name "unconnected-(U$2-9V-PadP$20)") (class "Default")
      (node (ref "U$2") (pin "P$20") (pinfunction "9V_P$20") (pintype "bidirectional"))
    )
    (net (code "113") (name "unconnected-(U$2-13-PadP$34)") (class "Default")
      (node (ref "U$2") (pin "P$34") (pinfunction "13_P$34") (pintype "bidirectional"))
    )
    (net (code "114") (name "unconnected-(U$2-A0-PadP$31)") (class "Default")
      (node (ref "U$2") (pin "P$31") (pinfunction "A0_P$31") (pintype "bidirectional"))
    )
    (net (code "115") (name "unconnected-(U$2-A1-PadP$30)") (class "Default")
      (node (ref "U$2") (pin "P$30") (pinfunction "A1_P$30") (pintype "bidirectional"))
    )
    (net (code "116") (name "unconnected-(U$2-A2-PadP$29)") (class "Default")
      (node (ref "U$2") (pin "P$29") (pinfunction "A2_P$29") (pintype "bidirectional"))
    )
    (net (code "117") (name "unconnected-(U$2-A3-PadP$28)") (class "Default")
      (node (ref "U$2") (pin "P$28") (pinfunction "A3_P$28") (pintype "bidirectional"))
    )
    (net (code "118") (name "unconnected-(U$2-A4-PadP$27)") (class "Default")
      (node (ref "U$2") (pin "P$27") (pinfunction "A4_P$27") (pintype "bidirectional"))
    )
    (net (code "119") (name "unconnected-(U$2-A5-PadP$26)") (class "Default")
      (node (ref "U$2") (pin "P$26") (pinfunction "A5_P$26") (pintype "bidirectional"))
    )
    (net (code "120") (name "unconnected-(U$2-AREF-PadP$32)") (class "Default")
      (node (ref "U$2") (pin "P$32") (pinfunction "AREF_P$32") (pintype "bidirectional"))
    )
    (net (code "121") (name "unconnected-(U$2-MISO-PadP$19)") (class "Default")
      (node (ref "U$2") (pin "P$19") (pinfunction "MISO_P$19") (pintype "bidirectional"))
    )
    (net (code "122") (name "unconnected-(U$2-MOSI-PadP$17)") (class "Default")
      (node (ref "U$2") (pin "P$17") (pinfunction "MOSI_P$17") (pintype "bidirectional"))
    )
    (net (code "123") (name "unconnected-(U$2-NC-PadP$24)") (class "Default")
      (node (ref "U$2") (pin "P$24") (pinfunction "NC_P$24") (pintype "bidirectional"))
    )
    (net (code "124") (name "unconnected-(U$2-NC-PadP$25)") (class "Default")
      (node (ref "U$2") (pin "P$25") (pinfunction "NC_P$25") (pintype "bidirectional"))
    )
    (net (code "125") (name "unconnected-(U$2-R-PadP$13)") (class "Default")
      (node (ref "U$2") (pin "P$13") (pinfunction "R_P$13") (pintype "bidirectional"))
    )
    (net (code "126") (name "unconnected-(U$2-R-PadP$22)") (class "Default")
      (node (ref "U$2") (pin "P$22") (pinfunction "R_P$22") (pintype "bidirectional"))
    )
    (net (code "127") (name "unconnected-(U$2-SCK-PadP$18)") (class "Default")
      (node (ref "U$2") (pin "P$18") (pinfunction "SCK_P$18") (pintype "bidirectional"))
    )
    (net (code "128") (name "unconnected-(U$2-SS-PadP$16)") (class "Default")
      (node (ref "U$2") (pin "P$16") (pinfunction "SS_P$16") (pintype "bidirectional"))
    )
  )
)
